# LSM6DS3.net
KiCad netlist of a schematic drawn in Altium Designer
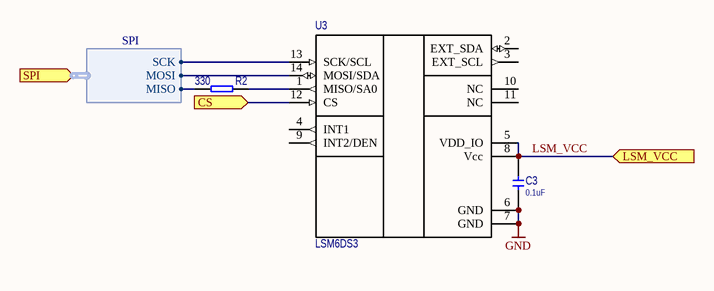
[diagram p0: LSM6DS3.SchDoc]

(export (version "E")
  (design (tool "Eeschema 10.0.6"))
  (components
    (comp (ref "C3")
      (value "0.1uF")
      (footprint "CERCAP 0402")
      (description "Capacitor")
      (fields (field (name "Comment") "CERCAP 0402 0.1uF * X7R"))
      (libsource (lib "!main") (part "!Capacitor"))
    )
    (comp (ref "R2")
      (value "330")
      (footprint "RES 0402")
      (description "Resistor")
      (fields (field (name "Comment") "RES 0402 330"))
      (libsource (lib "!main") (part "!Resistor"))
    )
    (comp (ref "U3")
      (value "LSM6DS3")
      (footprint "LGA14_LSM6DS3")
      (description "Acc/Gyro")
      (libsource (lib "sensors") (part "LSM6DS3"))
    )
  )
  (nets
    (net (code "2") (name "/CS") (class "Default")
      (node (ref "U3") (pin "12") (pinfunction "CS_12") (pintype "input"))
    )
    (net (code "3") (name "/LSM_VCC") (class "Default")
      (node (ref "C3") (pin "2") (pintype "passive"))
      (node (ref "U3") (pin "5") (pinfunction "VDD_IO_5") (pintype "power_in"))
      (node (ref "U3") (pin "8") (pinfunction "Vcc_8") (pintype "power_in"))
    )
    (net (code "4") (name "/MISO") (class "Default")
      (node (ref "R2") (pin "1") (pinfunction "11_1") (pintype "passive"))
    )
    (net (code "5") (name "/MOSI") (class "Default")
      (node (ref "U3") (pin "14") (pinfunction "MOSI/SDA_14") (pintype "bidirectional"))
    )
    (net (code "6") (name "/SCK") (class "Default")
      (node (ref "U3") (pin "13") (pinfunction "SCK/SCL_13") (pintype "input"))
    )
    (net (code "8") (name "GND") (class "Default")
      (node (ref "C3") (pin "1") (pintype "passive"))
      (node (ref "U3") (pin "6") (pinfunction "GND_6") (pintype "power_in"))
      (node (ref "U3") (pin "7") (pinfunction "GND_7") (pintype "power_in"))
    )
    (net (code "9") (name "Net-(R2-12)") (class "Default")
      (node (ref "R2") (pin "2") (pinfunction "12_2") (pintype "passive"))
      (node (ref "U3") (pin "1") (pinfunction "MISO/SA0_1") (pintype "output"))
    )
    (net (code "10") (name "unconnected-(U3-EXT_SCL-Pad3)") (class "Default")
      (node (ref "U3") (pin "3") (pinfunction "EXT_SCL_3") (pintype "output"))
    )
    (net (code "11") (name "unconnected-(U3-EXT_SDA-Pad2)") (class "Default")
      (node (ref "U3") (pin "2") (pinfunction "EXT_SDA_2") (pintype "bidirectional"))
    )
    (net (code "12") (name "unconnected-(U3-INT1-Pad4)") (class "Default")
      (node (ref "U3") (pin "4") (pinfunction "INT1_4") (pintype "output"))
    )
    (net (code "13") (name "unconnected-(U3-INT2{slash}DEN-Pad9)") (class "Default")
      (node (ref "U3") (pin "9") (pinfunction "INT2/DEN_9") (pintype "output"))
    )
    (net (code "14") (name "unconnected-(U3-NC-Pad10)") (class "Default")
      (node (ref "U3") (pin "10") (pinfunction "NC_10") (pintype "passive"))
    )
    (net (code "15") (name "unconnected-(U3-NC-Pad11)") (class "Default")
      (node (ref "U3") (pin "11") (pinfunction "NC_11") (pintype "passive"))
    )
  )
)
